# 8x8_matrix.net
KiCad netlist of a schematic drawn in EAGLE
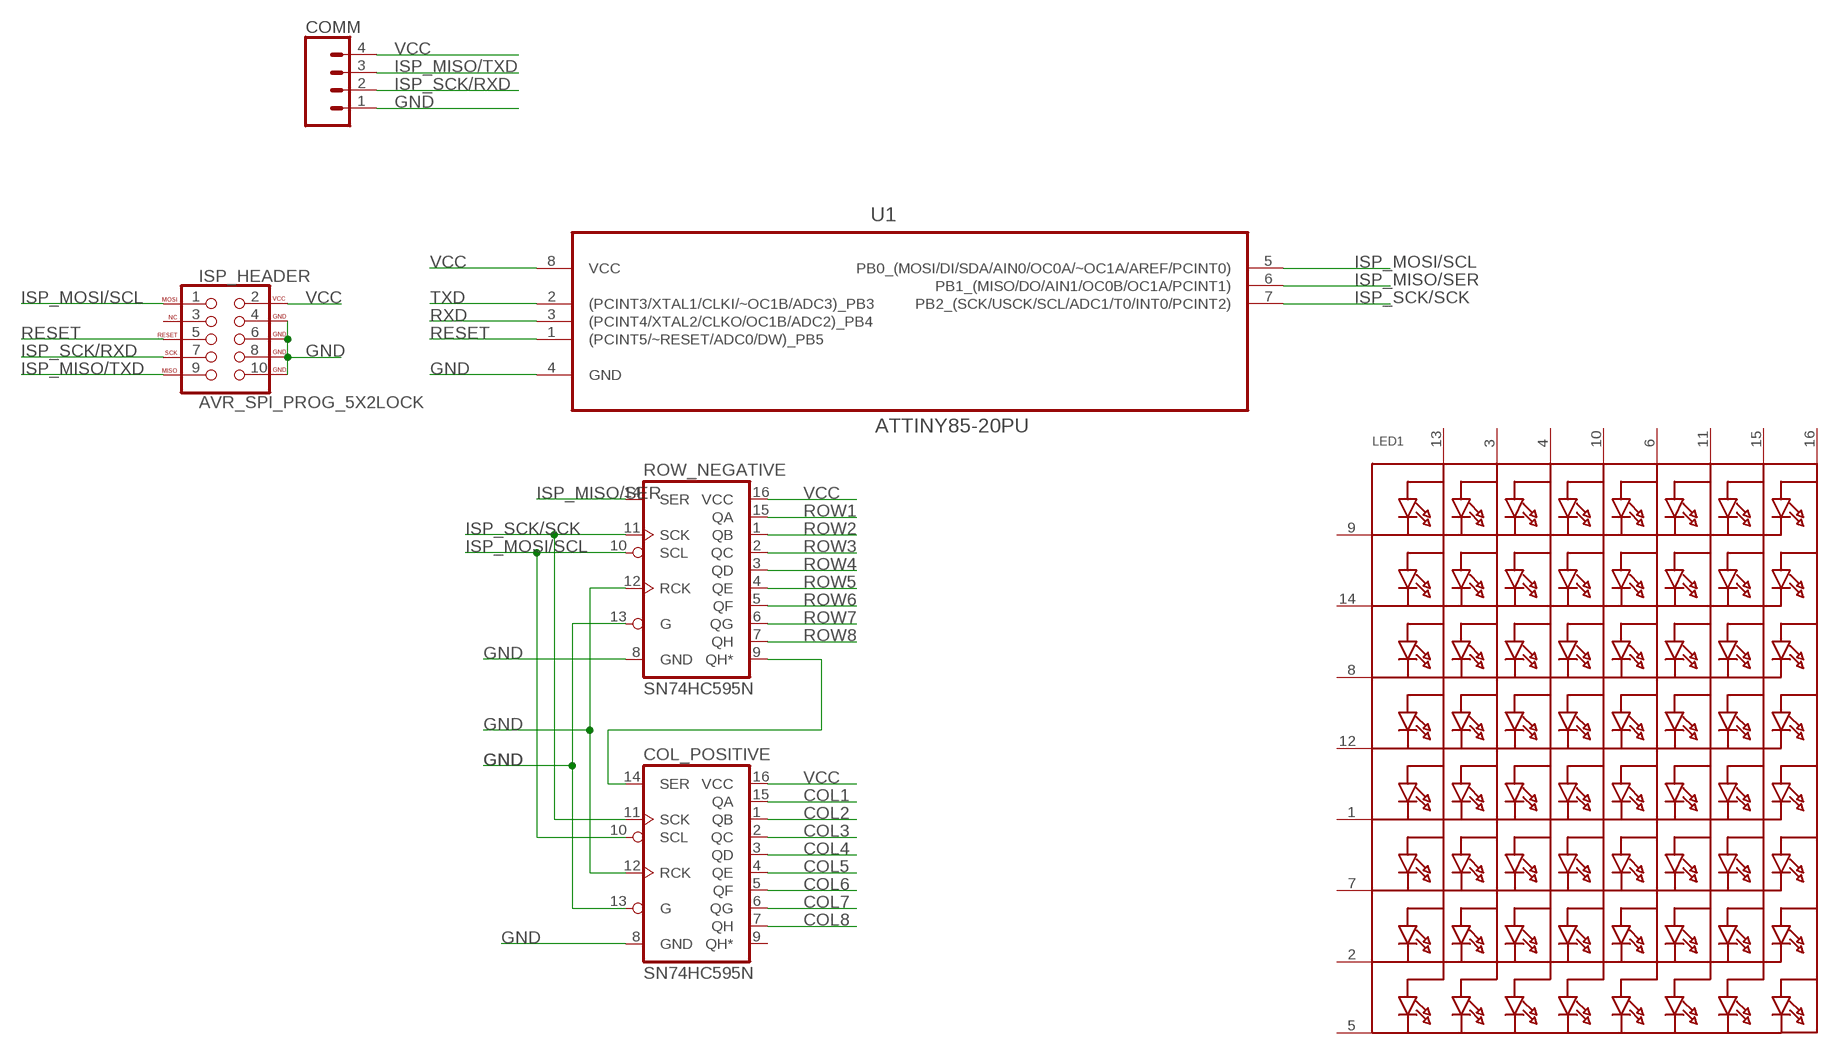
[diagram p0: schematic, sheet 1]

(export (version "E")
  (design (tool "Eeschema 10.0.6"))
  (components
    (comp (ref "COL_POSITIVE")
      (value "SN74HC595N")
      (footprint "eagle-import:DIP16")
      (libsource (lib "eagle-import") (part "74595NHC"))
    )
    (comp (ref "COMM")
      (value "CONN_04POLAR")
      (footprint "eagle-import:MOLEX-1X4")
      (libsource (lib "eagle-import") (part "CONN_04POLAR"))
    )
    (comp (ref "ISP_HEADER")
      (value "AVR_SPI_PROG_5X2LOCK")
      (footprint "eagle-import:2X5-SHROUDED_LOCK")
      (libsource (lib "eagle-import") (part "AVR_SPI_PROG_5X2LOCK"))
    )
    (comp (ref "LED1")
      (value "SEGMENT_8X8_ROWCATHODEM12A881UR")
      (footprint "eagle-import:SEGMENT_BL-M12A881UR")
      (libsource (lib "eagle-import") (part "SEGMENT_8X8_ROWCATHODEM12A881UR"))
    )
    (comp (ref "ROW_NEGATIVE")
      (value "SN74HC595N")
      (footprint "eagle-import:DIP16")
      (libsource (lib "eagle-import") (part "74595NHC"))
    )
    (comp (ref "U1")
      (value "ATTINY85-20PU")
      (footprint "eagle-import:DIP254P762X533-8")
      (libsource (lib "eagle-import") (part "ATTINY85-20PU"))
    )
  )
  (nets
    (net (code "1") (name "/COL1") (class "Default")
      (node (ref "COL_POSITIVE") (pin "15") (pinfunction "QA_15") (pintype "tri_state"))
    )
    (net (code "2") (name "/COL2") (class "Default")
      (node (ref "COL_POSITIVE") (pin "1") (pinfunction "QB_1") (pintype "tri_state"))
    )
    (net (code "3") (name "/COL3") (class "Default")
      (node (ref "COL_POSITIVE") (pin "2") (pinfunction "QC_2") (pintype "tri_state"))
    )
    (net (code "4") (name "/COL4") (class "Default")
      (node (ref "COL_POSITIVE") (pin "3") (pinfunction "QD_3") (pintype "tri_state"))
    )
    (net (code "5") (name "/COL5") (class "Default")
      (node (ref "COL_POSITIVE") (pin "4") (pinfunction "QE_4") (pintype "tri_state"))
    )
    (net (code "6") (name "/COL6") (class "Default")
      (node (ref "COL_POSITIVE") (pin "5") (pinfunction "QF_5") (pintype "tri_state"))
    )
    (net (code "7") (name "/COL7") (class "Default")
      (node (ref "COL_POSITIVE") (pin "6") (pinfunction "QG_6") (pintype "tri_state"))
    )
    (net (code "8") (name "/COL8") (class "Default")
      (node (ref "COL_POSITIVE") (pin "7") (pinfunction "QH_7") (pintype "tri_state"))
    )
    (net (code "9") (name "/GND") (class "Default")
      (node (ref "COL_POSITIVE") (pin "12") (pinfunction "RCK_12") (pintype "input"))
      (node (ref "COL_POSITIVE") (pin "13") (pinfunction "G_13") (pintype "input"))
      (node (ref "COL_POSITIVE") (pin "8") (pinfunction "GND_8") (pintype "power_in"))
      (node (ref "COMM") (pin "1") (pinfunction "1_1") (pintype "passive"))
      (node (ref "ISP_HEADER") (pin "10") (pinfunction "GND_10") (pintype "power_in"))
      (node (ref "ISP_HEADER") (pin "4") (pinfunction "GND_4") (pintype "power_in"))
      (node (ref "ISP_HEADER") (pin "6") (pinfunction "GND_6") (pintype "power_in"))
      (node (ref "ISP_HEADER") (pin "8") (pinfunction "GND_8") (pintype "power_in"))
      (node (ref "ROW_NEGATIVE") (pin "12") (pinfunction "RCK_12") (pintype "input"))
      (node (ref "ROW_NEGATIVE") (pin "13") (pinfunction "G_13") (pintype "input"))
      (node (ref "ROW_NEGATIVE") (pin "8") (pinfunction "GND_8") (pintype "power_in"))
      (node (ref "U1") (pin "4") (pinfunction "GND_4") (pintype "passive"))
    )
    (net (code "10") (name "/ISP_MISO{slash}SER") (class "Default")
      (node (ref "ROW_NEGATIVE") (pin "14") (pinfunction "SER_14") (pintype "input"))
      (node (ref "U1") (pin "6") (pinfunction "PB1_(MISO/DO/AIN1/OC0B/OC1A/PCINT1)_6") (pintype "bidirectional"))
    )
    (net (code "11") (name "/ISP_MISO{slash}TXD") (class "Default")
      (node (ref "COMM") (pin "3") (pinfunction "3_3") (pintype "passive"))
      (node (ref "ISP_HEADER") (pin "9") (pinfunction "MISO_9") (pintype "passive"))
    )
    (net (code "12") (name "/ISP_MOSI{slash}SCL") (class "Default")
      (node (ref "COL_POSITIVE") (pin "10") (pinfunction "SCL_10") (pintype "input"))
      (node (ref "ISP_HEADER") (pin "1") (pinfunction "MOSI_1") (pintype "passive"))
      (node (ref "ROW_NEGATIVE") (pin "10") (pinfunction "SCL_10") (pintype "input"))
      (node (ref "U1") (pin "5") (pinfunction "PB0_(MOSI/DI/SDA/AIN0/OC0A/~{OC1A/AREF/PCINT0})_5") (pintype "bidirectional"))
    )
    (net (code "13") (name "/ISP_SCK{slash}RXD") (class "Default")
      (node (ref "COMM") (pin "2") (pinfunction "2_2") (pintype "passive"))
      (node (ref "ISP_HEADER") (pin "7") (pinfunction "SCK_7") (pintype "passive"))
    )
    (net (code "14") (name "/ISP_SCK{slash}SCK") (class "Default")
      (node (ref "COL_POSITIVE") (pin "11") (pinfunction "SCK_11") (pintype "input"))
      (node (ref "ROW_NEGATIVE") (pin "11") (pinfunction "SCK_11") (pintype "input"))
      (node (ref "U1") (pin "7") (pinfunction "PB2_(SCK/USCK/SCL/ADC1/T0/INT0/PCINT2)_7") (pintype "bidirectional"))
    )
    (net (code "15") (name "/RESET") (class "Default")
      (node (ref "ISP_HEADER") (pin "5") (pinfunction "RESET_5") (pintype "passive"))
      (node (ref "U1") (pin "1") (pinfunction "(PCINT5/~{RESET/ADC0/DW})_PB5_1") (pintype "bidirectional"))
    )
    (net (code "16") (name "/ROW1") (class "Default")
      (node (ref "ROW_NEGATIVE") (pin "15") (pinfunction "QA_15") (pintype "tri_state"))
    )
    (net (code "17") (name "/ROW2") (class "Default")
      (node (ref "ROW_NEGATIVE") (pin "1") (pinfunction "QB_1") (pintype "tri_state"))
    )
    (net (code "18") (name "/ROW3") (class "Default")
      (node (ref "ROW_NEGATIVE") (pin "2") (pinfunction "QC_2") (pintype "tri_state"))
    )
    (net (code "19") (name "/ROW4") (class "Default")
      (node (ref "ROW_NEGATIVE") (pin "3") (pinfunction "QD_3") (pintype "tri_state"))
    )
    (net (code "20") (name "/ROW5") (class "Default")
      (node (ref "ROW_NEGATIVE") (pin "4") (pinfunction "QE_4") (pintype "tri_state"))
    )
    (net (code "21") (name "/ROW6") (class "Default")
      (node (ref "ROW_NEGATIVE") (pin "5") (pinfunction "QF_5") (pintype "tri_state"))
    )
    (net (code "22") (name "/ROW7") (class "Default")
      (node (ref "ROW_NEGATIVE") (pin "6") (pinfunction "QG_6") (pintype "tri_state"))
    )
    (net (code "23") (name "/ROW8") (class "Default")
      (node (ref "ROW_NEGATIVE") (pin "7") (pinfunction "QH_7") (pintype "tri_state"))
    )
    (net (code "24") (name "/RXD") (class "Default")
      (node (ref "U1") (pin "3") (pinfunction "(PCINT4/XTAL2/CLKO/OC1B/ADC2)_PB4_3") (pintype "bidirectional"))
    )
    (net (code "25") (name "/TXD") (class "Default")
      (node (ref "U1") (pin "2") (pinfunction "(PCINT3/XTAL1/CLKI/~{OC1B/ADC3})_PB3_2") (pintype "bidirectional"))
    )
    (net (code "26") (name "/VCC") (class "Default")
      (node (ref "COL_POSITIVE") (pin "16") (pinfunction "VCC_16") (pintype "power_in"))
      (node (ref "COMM") (pin "4") (pinfunction "4_4") (pintype "passive"))
      (node (ref "ISP_HEADER") (pin "2") (pinfunction "VCC_2") (pintype "power_in"))
      (node (ref "ROW_NEGATIVE") (pin "16") (pinfunction "VCC_16") (pintype "power_in"))
      (node (ref "U1") (pin "8") (pinfunction "VCC_8") (pintype "power_in"))
    )
    (net (code "27") (name "Net-(COL_POSITIVE-SER)") (class "Default")
      (node (ref "COL_POSITIVE") (pin "14") (pinfunction "SER_14") (pintype "input"))
      (node (ref "ROW_NEGATIVE") (pin "9") (pinfunction "QH*_9") (pintype "tri_state"))
    )
    (net (code "28") (name "unconnected-(COL_POSITIVE-QH*-Pad9)") (class "Default")
      (node (ref "COL_POSITIVE") (pin "9") (pinfunction "QH*_9") (pintype "tri_state"))
    )
    (net (code "29") (name "unconnected-(ISP_HEADER-NC-Pad3)") (class "Default")
      (node (ref "ISP_HEADER") (pin "3") (pinfunction "NC_3") (pintype "no_connect"))
    )
    (net (code "30") (name "unconnected-(LED1-A1-Pad13)") (class "Default")
      (node (ref "LED1") (pin "13") (pinfunction "A1_13") (pintype "bidirectional"))
    )
    (net (code "31") (name "unconnected-(LED1-A2-Pad3)") (class "Default")
      (node (ref "LED1") (pin "3") (pinfunction "A2_3") (pintype "bidirectional"))
    )
    (net (code "32") (name "unconnected-(LED1-A3-Pad4)") (class "Default")
      (node (ref "LED1") (pin "4") (pinfunction "A3_4") (pintype "bidirectional"))
    )
    (net (code "33") (name "unconnected-(LED1-A4-Pad10)") (class "Default")
      (node (ref "LED1") (pin "10") (pinfunction "A4_10") (pintype "bidirectional"))
    )
    (net (code "34") (name "unconnected-(LED1-A5-Pad6)") (class "Default")
      (node (ref "LED1") (pin "6") (pinfunction "A5_6") (pintype "bidirectional"))
    )
    (net (code "35") (name "unconnected-(LED1-A6-Pad11)") (class "Default")
      (node (ref "LED1") (pin "11") (pinfunction "A6_11") (pintype "bidirectional"))
    )
    (net (code "36") (name "unconnected-(LED1-A7-Pad15)") (class "Default")
      (node (ref "LED1") (pin "15") (pinfunction "A7_15") (pintype "bidirectional"))
    )
    (net (code "37") (name "unconnected-(LED1-A8-Pad16)") (class "Default")
      (node (ref "LED1") (pin "16") (pinfunction "A8_16") (pintype "bidirectional"))
    )
    (net (code "38") (name "unconnected-(LED1-K1-Pad9)") (class "Default")
      (node (ref "LED1") (pin "9") (pinfunction "K1_9") (pintype "bidirectional"))
    )
    (net (code "39") (name "unconnected-(LED1-K2-Pad14)") (class "Default")
      (node (ref "LED1") (pin "14") (pinfunction "K2_14") (pintype "bidirectional"))
    )
    (net (code "40") (name "unconnected-(LED1-K3-Pad8)") (class "Default")
      (node (ref "LED1") (pin "8") (pinfunction "K3_8") (pintype "bidirectional"))
    )
    (net (code "41") (name "unconnected-(LED1-K4-Pad12)") (class "Default")
      (node (ref "LED1") (pin "12") (pinfunction "K4_12") (pintype "bidirectional"))
    )
    (net (code "42") (name "unconnected-(LED1-K5-Pad1)") (class "Default")
      (node (ref "LED1") (pin "1") (pinfunction "K5_1") (pintype "bidirectional"))
    )
    (net (code "43") (name "unconnected-(LED1-K6-Pad7)") (class "Default")
      (node (ref "LED1") (pin "7") (pinfunction "K6_7") (pintype "bidirectional"))
    )
    (net (code "44") (name "unconnected-(LED1-K7-Pad2)") (class "Default")
      (node (ref "LED1") (pin "2") (pinfunction "K7_2") (pintype "bidirectional"))
    )
    (net (code "45") (name "unconnected-(LED1-K8-Pad5)") (class "Default")
      (node (ref "LED1") (pin "5") (pinfunction "K8_5") (pintype "bidirectional"))
    )
  )
)
